# wifi_ble.net
KiCad netlist of a schematic drawn in Altium Designer
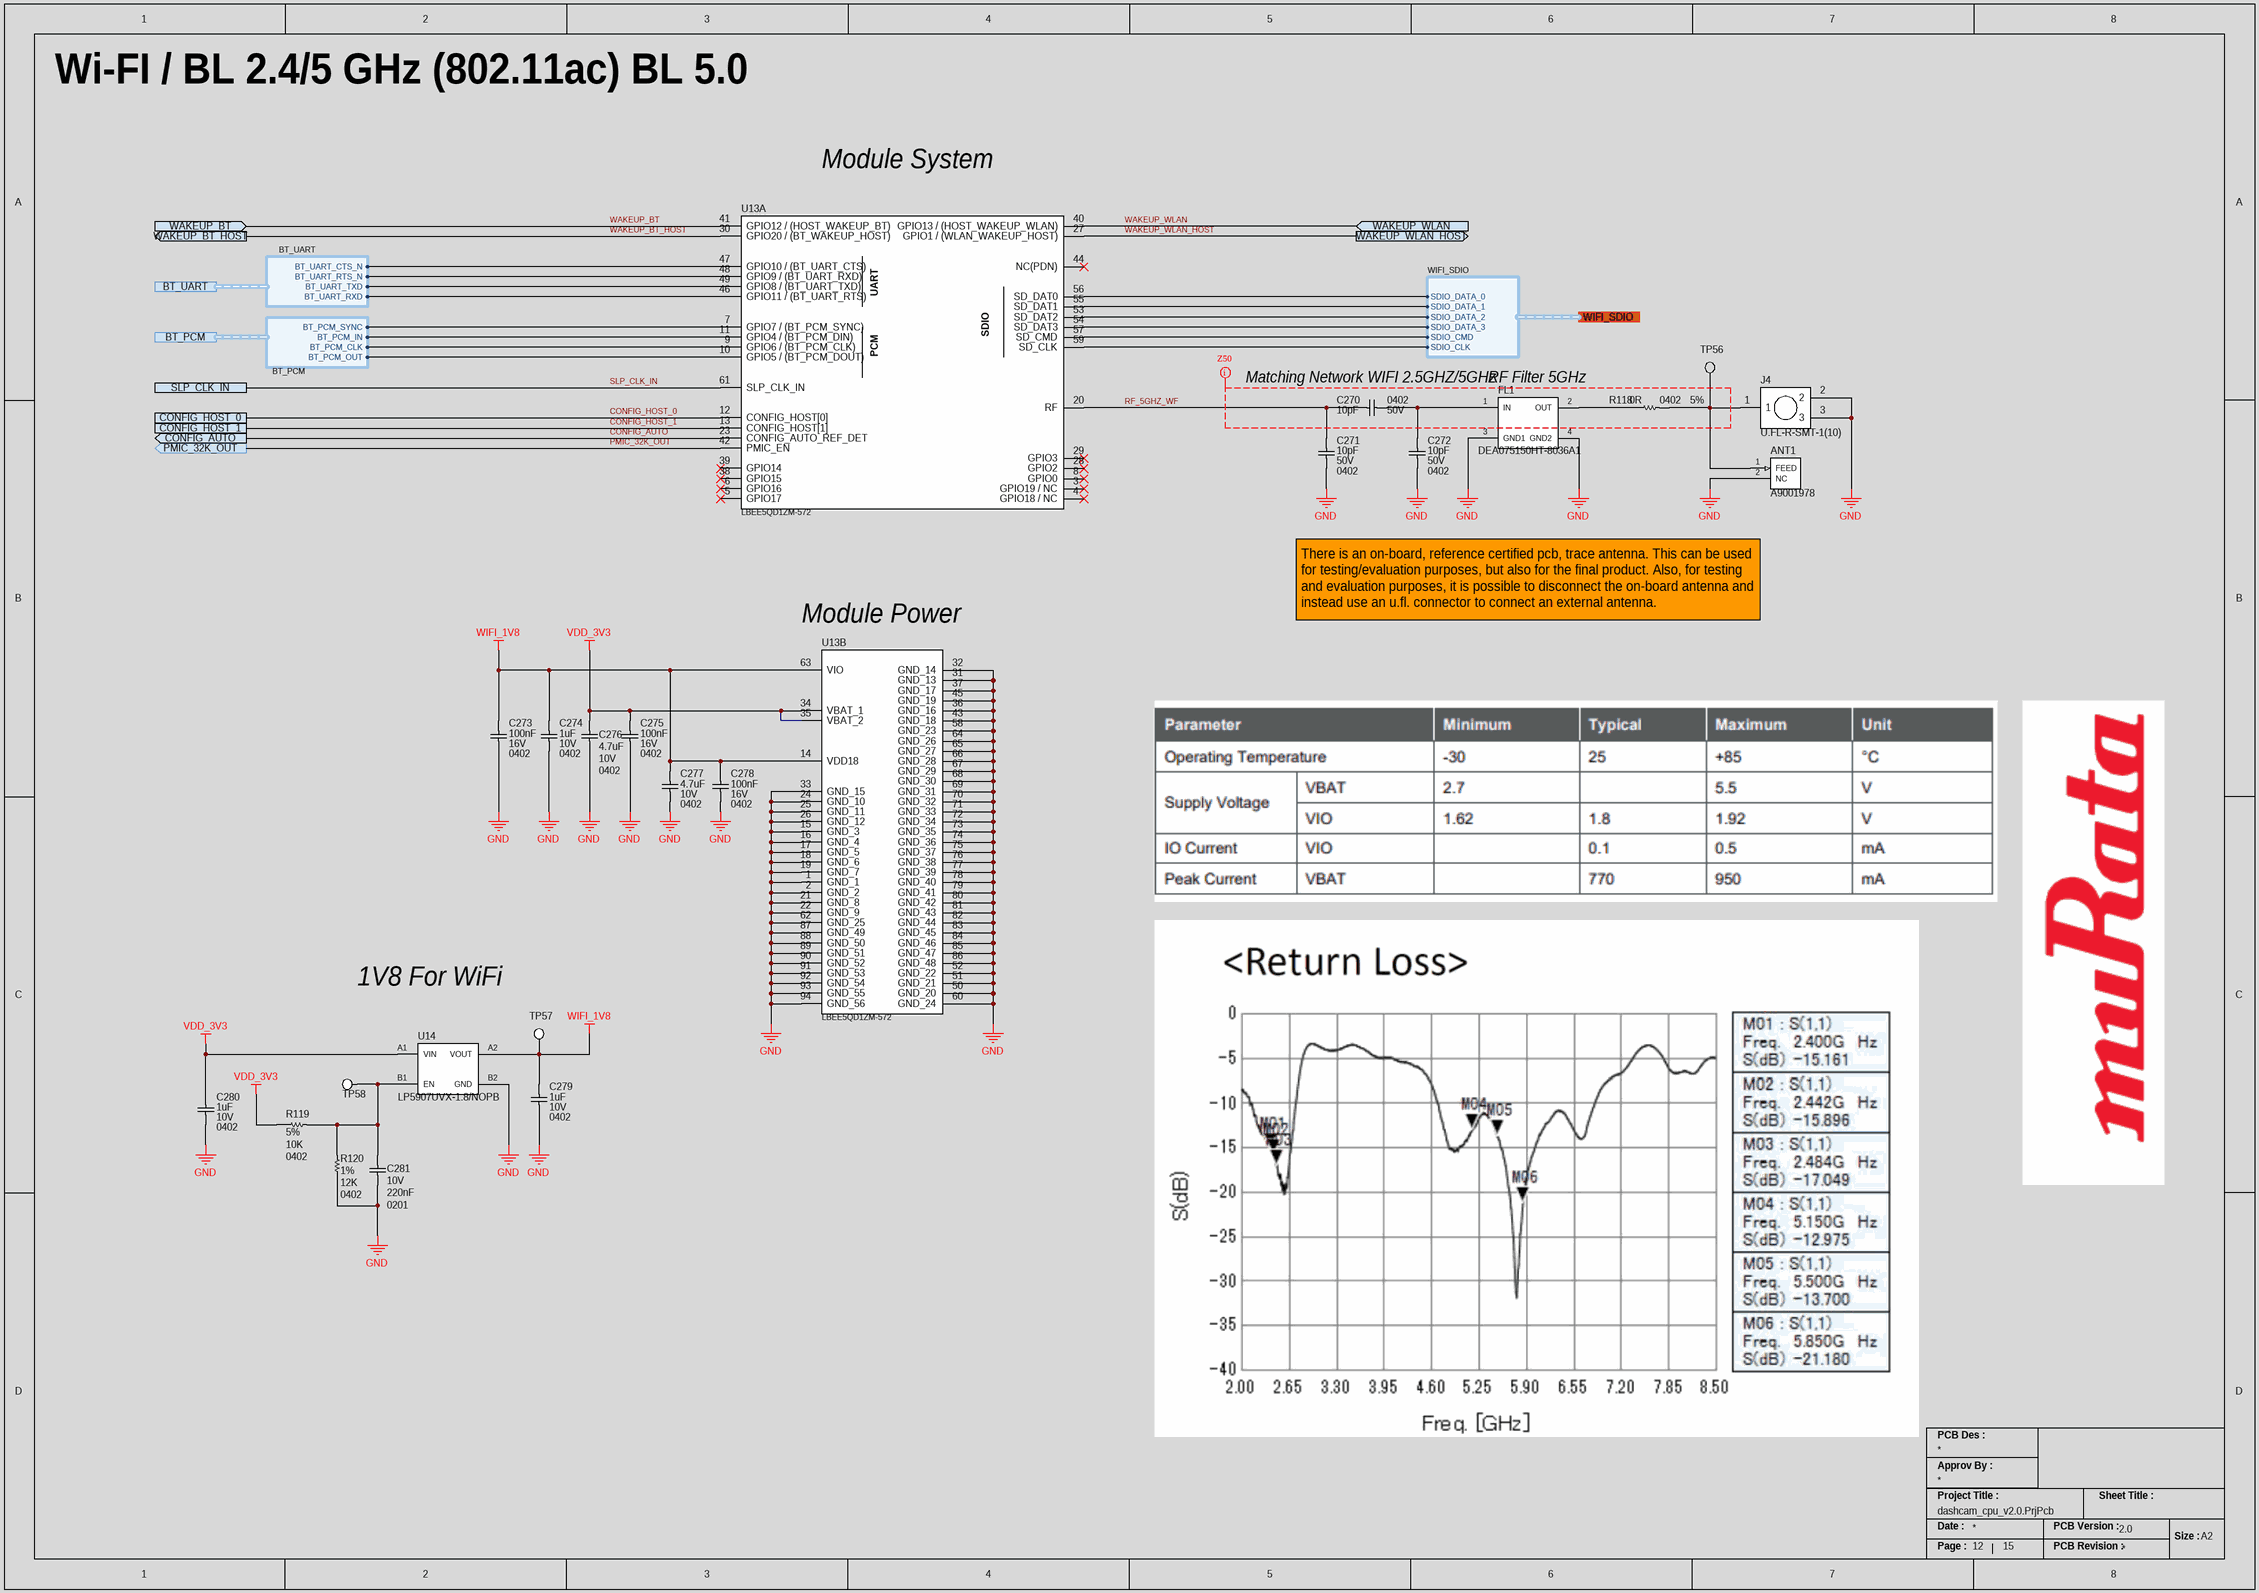
[diagram p0: wifi_ble.SchDoc]

(export (version "E")
  (design (tool "Eeschema 10.0.6"))
  (components
    (comp (ref "ANT1")
      (value "A9001978")
      (footprint "ANTENNA_CHIP_ANTC1006X50N")
      (description "Automotive Ultra-small Uwb Or Bl")
      (fields (field (name "MANUFACTURER") "Kyocera AVX"))
      (libsource (lib "Electronic Devices_LIB") (part "ANT_CHIP_2.5GHz_5GHz_A9001978"))
    )
    (comp (ref "C270")
      (value "GJM1555C1H100FB01D")
      (footprint "CAP_0402_CAPC1005X05N")
      (description "Multilayer Ceramic Capacitor, 10 pF, 50 V, ± 1%, C0G (NP0), 0402 [1005 Metric]")
      (fields
        (field (name "MANUFACTURER") "Murata")
        (field (name "TOLERANCE") "1%")
        (field (name "CASE/PACKAGE") "0402")
        (field (name "VOLTAGE RATING") "50V")
        (field (name "CAPACITANCE") "10pF")
      )
      (libsource (lib "Electronic Devices_LIB") (part "CAP_10PF_50V_NP0_0402"))
    )
    (comp (ref "C271")
      (value "GJM1555C1H100FB01D")
      (footprint "CAP_0402_CAPC1005X05N")
      (description "Multilayer Ceramic Capacitor, 10 pF, 50 V, ± 1%, C0G (NP0), 0402 [1005 Metric]")
      (fields
        (field (name "MANUFACTURER") "Murata")
        (field (name "TOLERANCE") "1%")
        (field (name "CASE/PACKAGE") "0402")
        (field (name "VOLTAGE RATING") "50V")
        (field (name "CAPACITANCE") "10pF")
      )
      (libsource (lib "Electronic Devices_LIB") (part "CAP_10PF_50V_NP0_0402"))
    )
    (comp (ref "C272")
      (value "GJM1555C1H100FB01D")
      (footprint "CAP_0402_CAPC1005X05N")
      (description "Multilayer Ceramic Capacitor, 10 pF, 50 V, ± 1%, C0G (NP0), 0402 [1005 Metric]")
      (fields
        (field (name "MANUFACTURER") "Murata")
        (field (name "TOLERANCE") "1%")
        (field (name "CASE/PACKAGE") "0402")
        (field (name "VOLTAGE RATING") "50V")
        (field (name "CAPACITANCE") "10pF")
      )
      (libsource (lib "Electronic Devices_LIB") (part "CAP_10PF_50V_NP0_0402"))
    )
    (comp (ref "C273")
      (value "CL05B104KO5NNNC")
      (footprint "CAP_0402_CAPC1005X05N")
      (description "Multilayer Ceramic Capacitor, 0.1 uF, 16 V, ± 10%, X7R, 0402 [1005 Metric]")
      (fields
        (field (name "MANUFACTURER") "Samsung")
        (field (name "TOLERANCE") "10%")
        (field (name "VOLTAGE RATING") "16V")
        (field (name "CAPACITANCE") "100nF")
        (field (name "CASE/PACKAGE") "0402")
      )
      (libsource (lib "Electronic Devices_LIB") (part "CAP_100NF_16V_X7R_0402"))
    )
    (comp (ref "C274")
      (value "GRM155C81A105KA12D")
      (footprint "CAP_0402_CAPC1005X05N")
      (description "0402 10 V 1 uF ±10% Tolerance X6S Multilayer Ceramic Capacitor")
      (fields
        (field (name "MANUFACTURER") "Murata")
        (field (name "TOLERANCE") "10%")
        (field (name "VOLTAGE RATING") "10V")
        (field (name "CAPACITANCE") "1uF")
        (field (name "CASE/PACKAGE") "0402")
      )
      (libsource (lib "Electronic Devices_LIB") (part "CAP_1UF_10V_X6S_0402"))
    )
    (comp (ref "C275")
      (value "CL05B104KO5NNNC")
      (footprint "CAP_0402_CAPC1005X05N")
      (description "Multilayer Ceramic Capacitor, 0.1 uF, 16 V, ± 10%, X7R, 0402 [1005 Metric]")
      (fields
        (field (name "MANUFACTURER") "Samsung")
        (field (name "TOLERANCE") "10%")
        (field (name "VOLTAGE RATING") "16V")
        (field (name "CAPACITANCE") "100nF")
        (field (name "CASE/PACKAGE") "0402")
      )
      (libsource (lib "Electronic Devices_LIB") (part "CAP_100NF_16V_X7R_0402"))
    )
    (comp (ref "C276")
      (value "CL05A475KP5NRNC")
      (footprint "CAP_0402_CAPC1005X05N")
      (description "Multilayer Ceramic Capacitor, 4.7 uF, 10 V, ± 10%, X5R, 0402 [1005 Metric]")
      (fields
        (field (name "MANUFACTURER") "Samsung")
        (field (name "TOLERANCE") "10%")
        (field (name "CAPACITANCE") "4.7uF")
        (field (name "VOLTAGE RATING") "10V")
        (field (name "CASE/PACKAGE") "0402")
      )
      (libsource (lib "Electronic Devices_LIB") (part "CAP_4.7UF_10V_X5R_0402"))
    )
    (comp (ref "C277")
      (value "CL05A475KP5NRNC")
      (footprint "CAP_0402_CAPC1005X05N")
      (description "Multilayer Ceramic Capacitor, 4.7 uF, 10 V, ± 10%, X5R, 0402 [1005 Metric]")
      (fields
        (field (name "MANUFACTURER") "Samsung")
        (field (name "TOLERANCE") "10%")
        (field (name "CAPACITANCE") "4.7uF")
        (field (name "VOLTAGE RATING") "10V")
        (field (name "CASE/PACKAGE") "0402")
      )
      (libsource (lib "Electronic Devices_LIB") (part "CAP_4.7UF_10V_X5R_0402"))
    )
    (comp (ref "C278")
      (value "CL05B104KO5NNNC")
      (footprint "CAP_0402_CAPC1005X05N")
      (description "Multilayer Ceramic Capacitor, 0.1 uF, 16 V, ± 10%, X7R, 0402 [1005 Metric]")
      (fields
        (field (name "MANUFACTURER") "Samsung")
        (field (name "TOLERANCE") "10%")
        (field (name "VOLTAGE RATING") "16V")
        (field (name "CAPACITANCE") "100nF")
        (field (name "CASE/PACKAGE") "0402")
      )
      (libsource (lib "Electronic Devices_LIB") (part "CAP_100NF_16V_X7R_0402"))
    )
    (comp (ref "C279")
      (value "GRM155C81A105KA12D")
      (footprint "CAP_0402_CAPC1005X05N")
      (description "0402 10 V 1 uF ±10% Tolerance X6S Multilayer Ceramic Capacitor")
      (fields
        (field (name "MANUFACTURER") "Murata")
        (field (name "TOLERANCE") "10%")
        (field (name "VOLTAGE RATING") "10V")
        (field (name "CAPACITANCE") "1uF")
        (field (name "CASE/PACKAGE") "0402")
      )
      (libsource (lib "Electronic Devices_LIB") (part "CAP_1UF_10V_X6S_0402"))
    )
    (comp (ref "C280")
      (value "GRM155C81A105KA12D")
      (footprint "CAP_0402_CAPC1005X05N")
      (description "0402 10 V 1 uF ±10% Tolerance X6S Multilayer Ceramic Capacitor")
      (fields
        (field (name "MANUFACTURER") "Murata")
        (field (name "TOLERANCE") "10%")
        (field (name "VOLTAGE RATING") "10V")
        (field (name "CAPACITANCE") "1uF")
        (field (name "CASE/PACKAGE") "0402")
      )
      (libsource (lib "Electronic Devices_LIB") (part "CAP_1UF_10V_X6S_0402"))
    )
    (comp (ref "C281")
      (value "LMK063BJ224MP-F")
      (footprint "CAP_0201_CAPC0603X03N")
      (description "Multilayer Ceramic Capacitors (High dielectric type), 10V, 0.22 uF, ± 20 %, 0201, X5R, RoHS")
      (fields
        (field (name "MANUFACTURER") "Taiyo Yuden")
        (field (name "TOLERANCE") "20%")
        (field (name "VOLTAGE RATING (DC)") "10V")
        (field (name "CAPACITANCE") "220nF")
        (field (name "CASE/PACKAGE") "0201")
      )
      (libsource (lib "Electronic Devices_LIB") (part "CAP_0.22UF_10V_X5R_0201"))
    )
    (comp (ref "FL1")
      (value "DEA075150HT-8036A1")
      (footprint "RF_FILTER_HP_DEA075150HT8036A1")
      (description "RF Filter High Pass 5150MHz 2400MHz to 2500MHz 0.5dB 50Ohm SMD 4Pin 0202 T/R")
      (fields (field (name "MANUFACTURER") "TDK"))
      (libsource (lib "Electronic Devices_LIB") (part "RF_FILTER_HIGH_PASS_DEA075150HT-8036A1"))
    )
    (comp (ref "J4")
      (value "U.FL-R-SMT-1(10)")
      (footprint "CONN_UFL_U.FL-R-SMT-1(10)")
      (description "RF Connector, 1 Contact(s), Male, Board Mount, Surface Mount Terminal, Receptacle")
      (fields (field (name "MANUFACTURER") "Hirose"))
      (libsource (lib "Electronic Devices_LIB") (part "CONN_UFL_RF_5OR_U.FL-R-SMT-1(10)"))
    )
    (comp (ref "R118")
      (value "ERJ-2GE0R00X")
      (footprint "RES_0402_RESC1005X04N")
      (description "SMD Chip Resistor, Jumper, 0 ohm, 100 mW, 0402 [1005 Metric], Thick Film, General Purpose")
      (fields
        (field (name "MANUFACTURER") "Panasonic")
        (field (name "CASE CODE (IMPERIAL)") "0402")
        (field (name "TOLERANCE") "5%")
        (field (name "RESISTANCE") "0R")
      )
      (libsource (lib "MGP Base_V1.0 RevA") (part "RES_0R_5%_100mW_0402"))
    )
    (comp (ref "R119")
      (value "ERJ-2GEJ103X")
      (footprint "RES_0402_RESC1005X04N")
      (description "Res Thick Film 0402 10K Ohm 5% 1/10W ±200ppm/°C Molded SMD Punched Carrier T/R")
      (fields
        (field (name "MANUFACTURER") "Panasonic")
        (field (name "TOLERANCE") "5%")
        (field (name "RESISTANCE") "10K")
        (field (name "CASE/PACKAGE") "0402")
      )
      (libsource (lib "Electronic Devices_LIB") (part "RES_10K_5%_100mW_0402"))
    )
    (comp (ref "R120")
      (value "ERJ-2RKF1202X")
      (footprint "RES_0402_RESC1005X04N")
      (description "Res Thick Film 0402 12K Ohm 1% 0.1W(1/10W) +/-100ppm/C Molded SMD Automotive Punched T/R")
      (fields
        (field (name "MANUFACTURER") "Panasonic")
        (field (name "TOLERANCE") "1%")
        (field (name "RESISTANCE") "12K")
        (field (name "CASE/PACKAGE") "0402")
      )
      (libsource (lib "Electronic Devices_LIB") (part "RES_12K_1%_100mW_0402"))
    )
    (comp (ref "TP56")
      (value "NO COMPONENT")
      (footprint "TP_PAD_0.5MM_SMD_ROUND")
      (description "Test Point, SMD pad, round, 1.5mm, 1.6mm, 3mm diameter")
      (libsource (lib "Electronic Devices_LIB") (part "TP_PAD_SMD_SMALL"))
    )
    (comp (ref "TP57")
      (value "NO COMPONENT")
      (footprint "TP_PAD_0.8MM_SMD_ROUND")
      (description "Test Point, SMD pad, round, 1.5mm, 1.6mm, 3mm diameter")
      (libsource (lib "Electronic Devices_LIB") (part "TP_PAD_SMD_Round"))
    )
    (comp (ref "TP58")
      (value "NO COMPONENT")
      (footprint "TP_PAD_0.8MM_SMD_ROUND")
      (description "Test Point, SMD pad, round, 1.5mm, 1.6mm, 3mm diameter")
      (libsource (lib "Electronic Devices_LIB") (part "TP_PAD_SMD_Round"))
    )
    (comp (ref "U13")
      (value "LBEE5QD1ZM-572")
      (footprint "IC_WIFI_BLE_LBEE5QD1ZM572")
      (description "2.4 to 5.825GHz Bluetooth WiFi 802.11a/b/g/-c, Bluetooth v5.1 Transceiver Module")
      (fields (field (name "MOUSER PART NUMBER") "81-LBEE5QD1ZM-572") (field (name "MANUFACTURER") "Murata"))
      (libsource (lib "Electronic Devices_LIB") (part "IC_WIFI_BLE_LBEE5QD1ZM-572"))
    )
    (comp (ref "U14")
      (value "LP5907UVX-1.8/NOPB")
      (footprint "IC_REG_LDO_BGA4C35P2X2_71X71X40")
      (description "Low Dropout Regulators(LDO) Positive Fixed 200mV @ 250mA 5.5V 1.8V 250mA DSBGA-4 RoHS")
      (fields (field (name "MANUFACTURER") "Texas Instruments"))
      (libsource (lib "Electronic Devices_LIB") (part "IC_REG_LDO_1.8V_250mA_LP5907UVX-1.8/NOPB"))
    )
  )
  (nets
    (net (code "4") (name "/BT_PCM_CLK") (class "Default")
      (node (ref "U13") (pin "9") (pinfunction "GPIO6_/_(BT_PCM_CLK)_9") (pintype "passive"))
    )
    (net (code "5") (name "/BT_PCM_IN") (class "Default")
      (node (ref "U13") (pin "11") (pinfunction "GPIO4_/_(BT_PCM_DIN)_11") (pintype "passive"))
    )
    (net (code "6") (name "/BT_PCM_OUT") (class "Default")
      (node (ref "U13") (pin "10") (pinfunction "GPIO5_/_(BT_PCM_DOUT)_10") (pintype "passive"))
    )
    (net (code "7") (name "/BT_PCM_SYNC") (class "Default")
      (node (ref "U13") (pin "7") (pinfunction "GPIO7_/_(BT_PCM_SYNC)_7") (pintype "passive"))
    )
    (net (code "8") (name "/BT_UART_CTS_N") (class "Default")
      (node (ref "U13") (pin "47") (pinfunction "GPIO10_/_(BT_UART_CTS)_47") (pintype "passive"))
    )
    (net (code "9") (name "/BT_UART_RTS_N") (class "Default")
      (node (ref "U13") (pin "48") (pinfunction "GPIO9_/_(BT_UART_RXD)_48") (pintype "passive"))
    )
    (net (code "10") (name "/BT_UART_RXD") (class "Default")
      (node (ref "U13") (pin "46") (pinfunction "GPIO11_/_(BT_UART_RTS)_46") (pintype "passive"))
    )
    (net (code "11") (name "/BT_UART_TXD") (class "Default")
      (node (ref "U13") (pin "49") (pinfunction "GPIO8_/_(BT_UART_TXD)_49") (pintype "passive"))
    )
    (net (code "12") (name "/CONFIG_AUTO") (class "Default")
      (node (ref "U13") (pin "23") (pinfunction "CONFIG_AUTO_REF_DET_23") (pintype "passive"))
    )
    (net (code "13") (name "/CONFIG_HOST_0") (class "Default")
      (node (ref "U13") (pin "12") (pinfunction "CONFIG_HOST[0]_12") (pintype "passive"))
    )
    (net (code "14") (name "/CONFIG_HOST_1") (class "Default")
      (node (ref "U13") (pin "13") (pinfunction "CONFIG_HOST[1]_13") (pintype "passive"))
    )
    (net (code "15") (name "/PMIC_32K_OUT") (class "Default")
      (node (ref "U13") (pin "42") (pinfunction "PMIC_EN_42") (pintype "passive"))
    )
    (net (code "16") (name "/RF_5GHZ_WF") (class "Default")
      (node (ref "C270") (pin "1") (pinfunction "1_1") (pintype "passive"))
      (node (ref "C271") (pin "2") (pinfunction "2_2") (pintype "passive"))
      (node (ref "U13") (pin "20") (pinfunction "RF_20") (pintype "passive"))
    )
    (net (code "17") (name "/SDIO_CLK") (class "Default")
      (node (ref "U13") (pin "59") (pinfunction "SD_CLK_59") (pintype "passive"))
    )
    (net (code "18") (name "/SDIO_CMD") (class "Default")
      (node (ref "U13") (pin "57") (pinfunction "SD_CMD_57") (pintype "passive"))
    )
    (net (code "19") (name "/SDIO_DATA_0") (class "Default")
      (node (ref "U13") (pin "56") (pinfunction "SD_DAT0_56") (pintype "passive"))
    )
    (net (code "20") (name "/SDIO_DATA_1") (class "Default")
      (node (ref "U13") (pin "55") (pinfunction "SD_DAT1_55") (pintype "passive"))
    )
    (net (code "21") (name "/SDIO_DATA_2") (class "Default")
      (node (ref "U13") (pin "53") (pinfunction "SD_DAT2_53") (pintype "passive"))
    )
    (net (code "22") (name "/SDIO_DATA_3") (class "Default")
      (node (ref "U13") (pin "54") (pinfunction "SD_DAT3_54") (pintype "passive"))
    )
    (net (code "23") (name "/SLP_CLK_IN") (class "Default")
      (node (ref "U13") (pin "61") (pinfunction "SLP_CLK_IN_61") (pintype "passive"))
    )
    (net (code "24") (name "/WAKEUP_BT") (class "Default")
      (node (ref "U13") (pin "41") (pinfunction "GPIO12_/_(HOST_WAKEUP_BT)_41") (pintype "passive"))
    )
    (net (code "25") (name "/WAKEUP_BT_HOST") (class "Default")
      (node (ref "U13") (pin "30") (pinfunction "GPIO20_/_(BT_WAKEUP_HOST)_30") (pintype "passive"))
    )
    (net (code "26") (name "/WAKEUP_WLAN") (class "Default")
      (node (ref "U13") (pin "40") (pinfunction "GPIO13_/_(HOST_WAKEUP_WLAN)_40") (pintype "passive"))
    )
    (net (code "27") (name "/WAKEUP_WLAN_HOST") (class "Default")
      (node (ref "U13") (pin "27") (pinfunction "GPIO1_/_(WLAN_WAKEUP_HOST)_27") (pintype "passive"))
    )
    (net (code "31") (name "GND") (class "Default")
      (node (ref "ANT1") (pin "2") (pinfunction "NC_2") (pintype "passive"))
      (node (ref "C271") (pin "1") (pinfunction "1_1") (pintype "passive"))
      (node (ref "C272") (pin "1") (pinfunction "1_1") (pintype "passive"))
      (node (ref "C273") (pin "1") (pinfunction "1_1") (pintype "passive"))
      (node (ref "C274") (pin "1") (pinfunction "1_1") (pintype "passive"))
      (node (ref "C275") (pin "1") (pinfunction "1_1") (pintype "passive"))
      (node (ref "C276") (pin "1") (pinfunction "1_1") (pintype "passive"))
      (node (ref "C277") (pin "1") (pinfunction "1_1") (pintype "passive"))
      (node (ref "C278") (pin "1") (pinfunction "1_1") (pintype "passive"))
      (node (ref "C279") (pin "1") (pinfunction "1_1") (pintype "passive"))
      (node (ref "C280") (pin "1") (pinfunction "1_1") (pintype "passive"))
      (node (ref "C281") (pin "1") (pinfunction "1_1") (pintype "passive"))
      (node (ref "FL1") (pin "3") (pinfunction "GND1_3") (pintype "passive"))
      (node (ref "FL1") (pin "4") (pinfunction "GND2_4") (pintype "passive"))
      (node (ref "J4") (pin "2") (pinfunction "2_2") (pintype "passive"))
      (node (ref "J4") (pin "3") (pinfunction "3_3") (pintype "passive"))
      (node (ref "R120") (pin "1") (pinfunction "1_1") (pintype "passive"))
      (node (ref "U13") (pin "1") (pinfunction "GND_1_1") (pintype "passive"))
      (node (ref "U13") (pin "15") (pinfunction "GND_3_15") (pintype "passive"))
      (node (ref "U13") (pin "16") (pinfunction "GND_4_16") (pintype "passive"))
      (node (ref "U13") (pin "17") (pinfunction "GND_5_17") (pintype "passive"))
      (node (ref "U13") (pin "18") (pinfunction "GND_6_18") (pintype "passive"))
      (node (ref "U13") (pin "19") (pinfunction "GND_7_19") (pintype "passive"))
      (node (ref "U13") (pin "2") (pinfunction "GND_2_2") (pintype "passive"))
      (node (ref "U13") (pin "21") (pinfunction "GND_8_21") (pintype "passive"))
      (node (ref "U13") (pin "22") (pinfunction "GND_9_22") (pintype "passive"))
      (node (ref "U13") (pin "24") (pinfunction "GND_10_24") (pintype "passive"))
      (node (ref "U13") (pin "25") (pinfunction "GND_11_25") (pintype "passive"))
      (node (ref "U13") (pin "26") (pinfunction "GND_12_26") (pintype "passive"))
      (node (ref "U13") (pin "31") (pinfunction "GND_13_31") (pintype "passive"))
      (node (ref "U13") (pin "32") (pinfunction "GND_14_32") (pintype "passive"))
      (node (ref "U13") (pin "33") (pinfunction "GND_15_33") (pintype "passive"))
      (node (ref "U13") (pin "36") (pinfunction "GND_16_36") (pintype "passive"))
      (node (ref "U13") (pin "37") (pinfunction "GND_17_37") (pintype "passive"))
      (node (ref "U13") (pin "43") (pinfunction "GND_18_43") (pintype "passive"))
      (node (ref "U13") (pin "45") (pinfunction "GND_19_45") (pintype "passive"))
      (node (ref "U13") (pin "50") (pinfunction "GND_20_50") (pintype "passive"))
      (node (ref "U13") (pin "51") (pinfunction "GND_21_51") (pintype "passive"))
      (node (ref "U13") (pin "52") (pinfunction "GND_22_52") (pintype "passive"))
      (node (ref "U13") (pin "58") (pinfunction "GND_23_58") (pintype "passive"))
      (node (ref "U13") (pin "60") (pinfunction "GND_24_60") (pintype "passive"))
      (node (ref "U13") (pin "62") (pinfunction "GND_25_62") (pintype "passive"))
      (node (ref "U13") (pin "64") (pinfunction "GND_26_64") (pintype "passive"))
      (node (ref "U13") (pin "65") (pinfunction "GND_27_65") (pintype "passive"))
      (node (ref "U13") (pin "66") (pinfunction "GND_28_66") (pintype "passive"))
      (node (ref "U13") (pin "67") (pinfunction "GND_29_67") (pintype "passive"))
      (node (ref "U13") (pin "68") (pinfunction "GND_30_68") (pintype "passive"))
      (node (ref "U13") (pin "69") (pinfunction "GND_31_69") (pintype "passive"))
      (node (ref "U13") (pin "70") (pinfunction "GND_32_70") (pintype "passive"))
      (node (ref "U13") (pin "71") (pinfunction "GND_33_71") (pintype "passive"))
      (node (ref "U13") (pin "72") (pinfunction "GND_34_72") (pintype "passive"))
      (node (ref "U13") (pin "73") (pinfunction "GND_35_73") (pintype "passive"))
      (node (ref "U13") (pin "74") (pinfunction "GND_36_74") (pintype "passive"))
      (node (ref "U13") (pin "75") (pinfunction "GND_37_75") (pintype "passive"))
      (node (ref "U13") (pin "76") (pinfunction "GND_38_76") (pintype "passive"))
      (node (ref "U13") (pin "77") (pinfunction "GND_39_77") (pintype "passive"))
      (node (ref "U13") (pin "78") (pinfunction "GND_40_78") (pintype "passive"))
      (node (ref "U13") (pin "79") (pinfunction "GND_41_79") (pintype "passive"))
      (node (ref "U13") (pin "80") (pinfunction "GND_42_80") (pintype "passive"))
      (node (ref "U13") (pin "81") (pinfunction "GND_43_81") (pintype "passive"))
      (node (ref "U13") (pin "82") (pinfunction "GND_44_82") (pintype "passive"))
      (node (ref "U13") (pin "83") (pinfunction "GND_45_83") (pintype "passive"))
      (node (ref "U13") (pin "84") (pinfunction "GND_46_84") (pintype "passive"))
      (node (ref "U13") (pin "85") (pinfunction "GND_47_85") (pintype "passive"))
      (node (ref "U13") (pin "86") (pinfunction "GND_48_86") (pintype "passive"))
      (node (ref "U13") (pin "87") (pinfunction "GND_49_87") (pintype "passive"))
      (node (ref "U13") (pin "88") (pinfunction "GND_50_88") (pintype "passive"))
      (node (ref "U13") (pin "89") (pinfunction "GND_51_89") (pintype "passive"))
      (node (ref "U13") (pin "90") (pinfunction "GND_52_90") (pintype "passive"))
      (node (ref "U13") (pin "91") (pinfunction "GND_53_91") (pintype "passive"))
      (node (ref "U13") (pin "92") (pinfunction "GND_54_92") (pintype "passive"))
      (node (ref "U13") (pin "93") (pinfunction "GND_55_93") (pintype "passive"))
      (node (ref "U13") (pin "94") (pinfunction "GND_56_94") (pintype "passive"))
      (node (ref "U14") (pin "B2") (pinfunction "GND_B2") (pintype "passive"))
    )
    (net (code "32") (name "Net-(ANT1-FEED)") (class "Default")
      (node (ref "ANT1") (pin "1") (pinfunction "FEED_1") (pintype "input"))
      (node (ref "J4") (pin "1") (pinfunction "1_1") (pintype "passive"))
      (node (ref "R118") (pin "2") (pinfunction "2_2") (pintype "passive"))
      (node (ref "TP56") (pin "1") (pinfunction "1_1") (pintype "passive"))
    )
    (net (code "33") (name "Net-(FL1-IN)") (class "Default")
      (node (ref "C270") (pin "2") (pinfunction "2_2") (pintype "passive"))
      (node (ref "C272") (pin "2") (pinfunction "2_2") (pintype "passive"))
      (node (ref "FL1") (pin "1") (pinfunction "IN_1") (pintype "passive"))
    )
    (net (code "34") (name "Net-(FL1-OUT)") (class "Default")
      (node (ref "FL1") (pin "2") (pinfunction "OUT_2") (pintype "passive"))
      (node (ref "R118") (pin "1") (pinfunction "1_1") (pintype "passive"))
    )
    (net (code "35") (name "Net-(U14-EN)") (class "Default")
      (node (ref "C281") (pin "2") (pinfunction "2_2") (pintype "passive"))
      (node (ref "R119") (pin "2") (pinfunction "2_2") (pintype "passive"))
      (node (ref "R120") (pin "2") (pinfunction "2_2") (pintype "passive"))
      (node (ref "TP58") (pin "1") (pinfunction "1_1") (pintype "passive"))
      (node (ref "U14") (pin "B1") (pinfunction "EN_B1") (pintype "passive"))
    )
    (net (code "36") (name "VDD_3V3") (class "Default")
      (node (ref "C275") (pin "2") (pinfunction "2_2") (pintype "passive"))
      (node (ref "C276") (pin "2") (pinfunction "2_2") (pintype "passive"))
      (node (ref "C280") (pin "2") (pinfunction "2_2") (pintype "passive"))
      (node (ref "R119") (pin "1") (pinfunction "1_1") (pintype "passive"))
      (node (ref "U13") (pin "34") (pinfunction "VBAT_1_34") (pintype "passive"))
      (node (ref "U13") (pin "35") (pinfunction "VBAT_2_35") (pintype "passive"))
      (node (ref "U14") (pin "A1") (pinfunction "VIN_A1") (pintype "passive"))
    )
    (net (code "37") (name "WIFI_1V8") (class "Default")
      (node (ref "C273") (pin "2") (pinfunction "2_2") (pintype "passive"))
      (node (ref "C274") (pin "2") (pinfunction "2_2") (pintype "passive"))
      (node (ref "C277") (pin "2") (pinfunction "2_2") (pintype "passive"))
      (node (ref "C278") (pin "2") (pinfunction "2_2") (pintype "passive"))
      (node (ref "C279") (pin "2") (pinfunction "2_2") (pintype "passive"))
      (node (ref "TP57") (pin "1") (pinfunction "1_1") (pintype "passive"))
      (node (ref "U13") (pin "14") (pinfunction "VDD18_14") (pintype "passive"))
      (node (ref "U13") (pin "63") (pinfunction "VIO_63") (pintype "passive"))
      (node (ref "U14") (pin "A2") (pinfunction "VOUT_A2") (pintype "passive"))
    )
    (net (code "38") (name "unconnected-(U13A-GPIO0-Pad8)") (class "Default")
      (node (ref "U13") (pin "8") (pinfunction "GPIO0_8") (pintype "passive+no_connect"))
    )
    (net (code "39") (name "unconnected-(U13A-GPIO2-Pad28)") (class "Default")
      (node (ref "U13") (pin "28") (pinfunction "GPIO2_28") (pintype "passive+no_connect"))
    )
    (net (code "40") (name "unconnected-(U13A-GPIO3-Pad29)") (class "Default")
      (node (ref "U13") (pin "29") (pinfunction "GPIO3_29") (pintype "passive+no_connect"))
    )
    (net (code "41") (name "unconnected-(U13A-GPIO14-Pad39)") (class "Default")
      (node (ref "U13") (pin "39") (pinfunction "GPIO14_39") (pintype "passive+no_connect"))
    )
    (net (code "42") (name "unconnected-(U13A-GPIO15-Pad38)") (class "Default")
      (node (ref "U13") (pin "38") (pinfunction "GPIO15_38") (pintype "passive+no_connect"))
    )
    (net (code "43") (name "unconnected-(U13A-GPIO16-Pad6)") (class "Default")
      (node (ref "U13") (pin "6") (pinfunction "GPIO16_6") (pintype "passive+no_connect"))
    )
    (net (code "44") (name "unconnected-(U13A-GPIO17-Pad5)") (class "Default")
      (node (ref "U13") (pin "5") (pinfunction "GPIO17_5") (pintype "passive+no_connect"))
    )
    (net (code "45") (name "unconnected-(U13A-GPIO18_{slash}_NC-Pad4)") (class "Default")
      (node (ref "U13") (pin "4") (pinfunction "GPIO18_/_NC_4") (pintype "passive+no_connect"))
    )
    (net (code "46") (name "unconnected-(U13A-GPIO19_{slash}_NC-Pad3)") (class "Default")
      (node (ref "U13") (pin "3") (pinfunction "GPIO19_/_NC_3") (pintype "passive+no_connect"))
    )
    (net (code "47") (name "unconnected-(U13A-NC(PDN)-Pad44)") (class "Default")
      (node (ref "U13") (pin "44") (pinfunction "NC(PDN)_44") (pintype "passive+no_connect"))
    )
  )
)
